# pattern_game.net
KiCad netlist of a schematic drawn in EAGLE
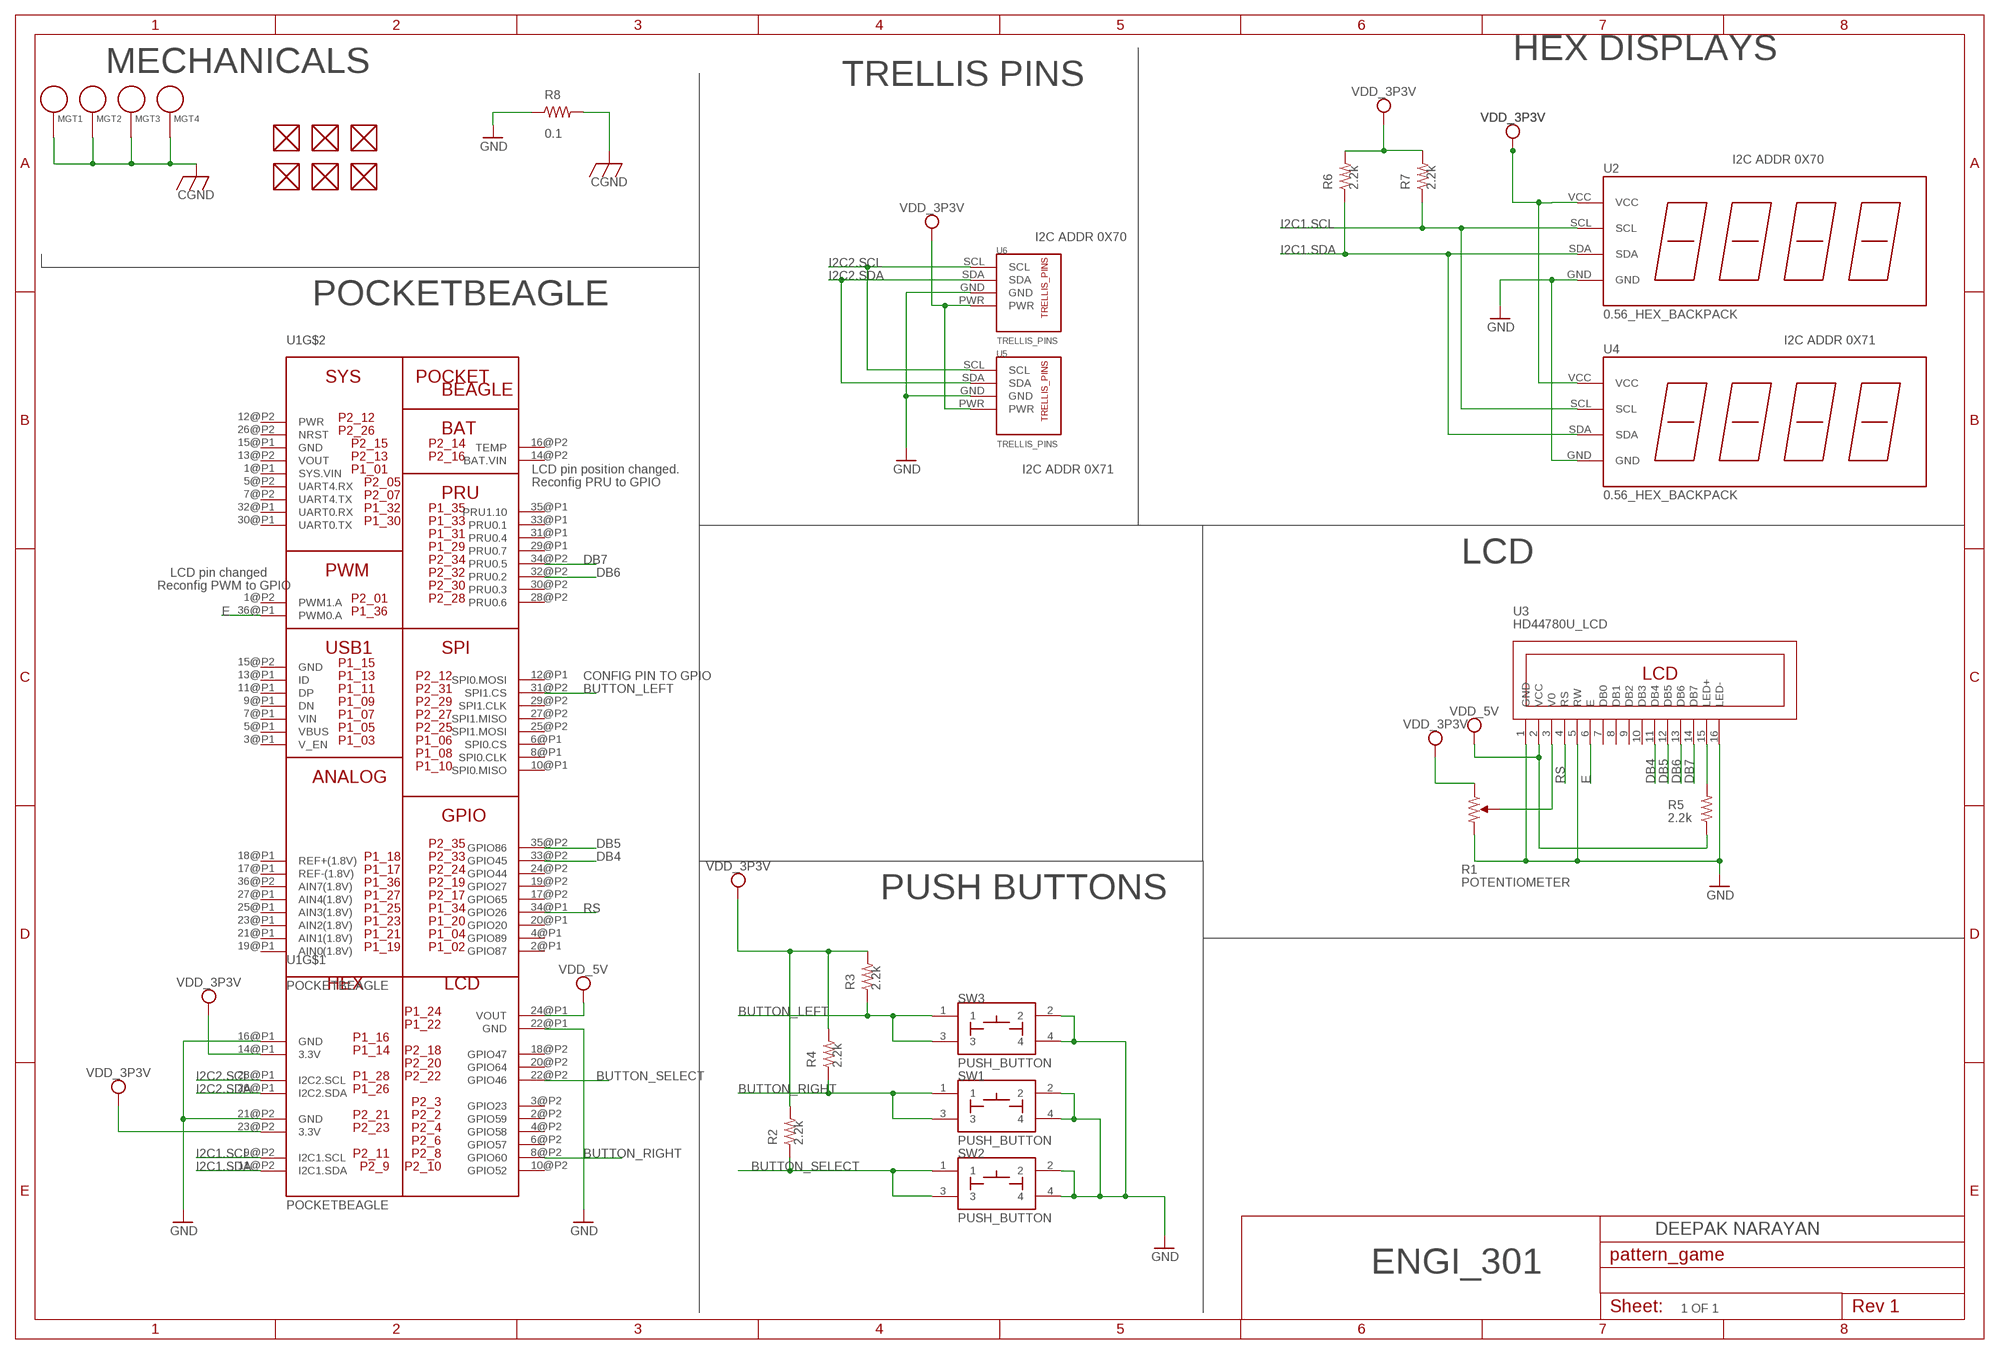
[diagram p0: schematic, sheet 1]

(export (version "E")
  (design (tool "Eeschema 10.0.6"))
  (components
    (comp (ref "FUD1")
      (value "FIDUCIAL")
      (footprint "eagle-import:FIDUCIAL_40MIL")
      (libsource (lib "eagle-import") (part "FIDUCIAL"))
    )
    (comp (ref "FUD2")
      (value "FIDUCIAL")
      (footprint "eagle-import:FIDUCIAL_40MIL")
      (libsource (lib "eagle-import") (part "FIDUCIAL"))
    )
    (comp (ref "FUD3")
      (value "FIDUCIAL")
      (footprint "eagle-import:FIDUCIAL_40MIL")
      (libsource (lib "eagle-import") (part "FIDUCIAL"))
    )
    (comp (ref "FUD4")
      (value "FIDUCIAL")
      (footprint "eagle-import:FIDUCIAL_40MIL")
      (libsource (lib "eagle-import") (part "FIDUCIAL"))
    )
    (comp (ref "FUD5")
      (value "FIDUCIAL")
      (footprint "eagle-import:FIDUCIAL_40MIL")
      (libsource (lib "eagle-import") (part "FIDUCIAL"))
    )
    (comp (ref "FUD6")
      (value "FIDUCIAL")
      (footprint "eagle-import:FIDUCIAL_40MIL")
      (libsource (lib "eagle-import") (part "FIDUCIAL"))
    )
    (comp (ref "MGT1")
      (value "MOUNTING_HOLE")
      (footprint "eagle-import:MOUNTING_HOLE")
      (libsource (lib "eagle-import") (part "MOUNTING_HOLE"))
    )
    (comp (ref "MGT2")
      (value "MOUNTING_HOLE")
      (footprint "eagle-import:MOUNTING_HOLE")
      (libsource (lib "eagle-import") (part "MOUNTING_HOLE"))
    )
    (comp (ref "MGT3")
      (value "MOUNTING_HOLE")
      (footprint "eagle-import:MOUNTING_HOLE")
      (libsource (lib "eagle-import") (part "MOUNTING_HOLE"))
    )
    (comp (ref "MGT4")
      (value "MOUNTING_HOLE")
      (footprint "eagle-import:MOUNTING_HOLE")
      (libsource (lib "eagle-import") (part "MOUNTING_HOLE"))
    )
    (comp (ref "R1")
      (value "POTENTIOMETER")
      (footprint "eagle-import:POT-PO90S")
      (libsource (lib "eagle-import") (part "POTENTIOMETER"))
    )
    (comp (ref "R2")
      (value "2.2k")
      (footprint "eagle-import:R0603")
      (libsource (lib "eagle-import") (part "R_R0603"))
    )
    (comp (ref "R3")
      (value "2.2k")
      (footprint "eagle-import:R0603")
      (libsource (lib "eagle-import") (part "R_R0603"))
    )
    (comp (ref "R4")
      (value "2.2k")
      (footprint "eagle-import:R0603")
      (libsource (lib "eagle-import") (part "R_R0603"))
    )
    (comp (ref "R5")
      (value "2.2k")
      (footprint "eagle-import:R0603")
      (libsource (lib "eagle-import") (part "R_R0603"))
    )
    (comp (ref "R6")
      (value "2.2k")
      (footprint "eagle-import:R0603")
      (libsource (lib "eagle-import") (part "R_R0603"))
    )
    (comp (ref "R7")
      (value "2.2k")
      (footprint "eagle-import:R0603")
      (libsource (lib "eagle-import") (part "R_R0603"))
    )
    (comp (ref "R8")
      (value "0.1")
      (footprint "eagle-import:R0603")
      (libsource (lib "eagle-import") (part "combo_lock_R_R0603"))
    )
    (comp (ref "SW1")
      (value "PUSH_BUTTON")
      (footprint "eagle-import:BUTTON_12.5MM")
      (libsource (lib "eagle-import") (part "PUSH_BUTTON"))
    )
    (comp (ref "SW2")
      (value "PUSH_BUTTON")
      (footprint "eagle-import:BUTTON_12.5MM")
      (libsource (lib "eagle-import") (part "PUSH_BUTTON"))
    )
    (comp (ref "SW3")
      (value "PUSH_BUTTON")
      (footprint "eagle-import:BUTTON_12.5MM")
      (libsource (lib "eagle-import") (part "PUSH_BUTTON"))
    )
    (comp (ref "U1")
      (value "POCKETBEAGLE")
      (footprint "eagle-import:POCKETBEAGLE")
      (libsource (lib "eagle-import") (part "POCKETBEAGLE"))
    )
    (comp (ref "U2")
      (value "0.56_HEX_BACKPACK")
      (footprint "eagle-import:0.56_HEX_BACKPACK")
      (libsource (lib "eagle-import") (part "0.56_HEX_BACKPACK"))
    )
    (comp (ref "U3")
      (value "HD44780U_LCD")
      (footprint "eagle-import:HD44780U_LCD")
      (libsource (lib "eagle-import") (part "HD44780U_LCD"))
    )
    (comp (ref "U4")
      (value "0.56_HEX_BACKPACK")
      (footprint "eagle-import:0.56_HEX_BACKPACK")
      (libsource (lib "eagle-import") (part "0.56_HEX_BACKPACK"))
    )
    (comp (ref "U5")
      (value "TRELLIS_PINS")
      (footprint "eagle-import:TRELLIS_PINS")
      (libsource (lib "eagle-import") (part "TRELLIS_PINS"))
    )
    (comp (ref "U6")
      (value "TRELLIS_PINS")
      (footprint "eagle-import:TRELLIS_PINS")
      (libsource (lib "eagle-import") (part "TRELLIS_PINS"))
    )
  )
  (nets
    (net (code "1") (name "/BUTTON_LEFT") (class "Default")
      (node (ref "R3") (pin "1") (pinfunction "1_1") (pintype "passive"))
      (node (ref "SW3") (pin "1") (pinfunction "1_1") (pintype "bidirectional"))
      (node (ref "SW3") (pin "3") (pinfunction "3_3") (pintype "bidirectional"))
      (node (ref "U1") (pin "31@P2") (pinfunction "SPI1.CS_31@P2") (pintype "bidirectional"))
    )
    (net (code "2") (name "/BUTTON_RIGHT") (class "Default")
      (node (ref "R4") (pin "1") (pinfunction "1_1") (pintype "passive"))
      (node (ref "SW1") (pin "1") (pinfunction "1_1") (pintype "bidirectional"))
      (node (ref "SW1") (pin "3") (pinfunction "3_3") (pintype "bidirectional"))
      (node (ref "U1") (pin "8@P2") (pinfunction "GPIO60_8@P2") (pintype "bidirectional"))
    )
    (net (code "3") (name "/BUTTON_SELECT") (class "Default")
      (node (ref "R2") (pin "1") (pinfunction "1_1") (pintype "passive"))
      (node (ref "SW2") (pin "1") (pinfunction "1_1") (pintype "bidirectional"))
      (node (ref "SW2") (pin "3") (pinfunction "3_3") (pintype "bidirectional"))
      (node (ref "U1") (pin "22@P2") (pinfunction "GPIO46_22@P2") (pintype "bidirectional"))
    )
    (net (code "4") (name "/DB4") (class "Default")
      (node (ref "U1") (pin "33@P2") (pinfunction "GPIO45_33@P2") (pintype "bidirectional"))
      (node (ref "U3") (pin "11") (pinfunction "DB4_11") (pintype "bidirectional"))
    )
    (net (code "5") (name "/DB5") (class "Default")
      (node (ref "U1") (pin "35@P2") (pinfunction "GPIO86_35@P2") (pintype "bidirectional"))
      (node (ref "U3") (pin "12") (pinfunction "DB5_12") (pintype "bidirectional"))
    )
    (net (code "6") (name "/DB6") (class "Default")
      (node (ref "U1") (pin "32@P2") (pinfunction "PRU0.2_32@P2") (pintype "bidirectional"))
      (node (ref "U3") (pin "13") (pinfunction "DB6_13") (pintype "bidirectional"))
    )
    (net (code "7") (name "/DB7") (class "Default")
      (node (ref "U1") (pin "34@P2") (pinfunction "PRU0.5_34@P2") (pintype "bidirectional"))
      (node (ref "U3") (pin "14") (pinfunction "DB7_14") (pintype "bidirectional"))
    )
    (net (code "8") (name "/E") (class "Default")
      (node (ref "U1") (pin "36@P1") (pinfunction "PWM0.A_36@P1") (pintype "bidirectional"))
      (node (ref "U3") (pin "6") (pinfunction "E_6") (pintype "bidirectional"))
    )
    (net (code "9") (name "/I2C1.SCL") (class "Default")
      (node (ref "R7") (pin "1") (pinfunction "1_1") (pintype "passive"))
      (node (ref "U1") (pin "9@P2") (pinfunction "I2C1.SCL_9@P2") (pintype "bidirectional"))
      (node (ref "U2") (pin "SCL") (pinfunction "SCL_SCL") (pintype "bidirectional"))
      (node (ref "U4") (pin "SCL") (pinfunction "SCL_SCL") (pintype "bidirectional"))
    )
    (net (code "10") (name "/I2C1.SDA") (class "Default")
      (node (ref "R6") (pin "1") (pinfunction "1_1") (pintype "passive"))
      (node (ref "U1") (pin "11@P2") (pinfunction "I2C1.SDA_11@P2") (pintype "bidirectional"))
      (node (ref "U2") (pin "SDA") (pinfunction "SDA_SDA") (pintype "bidirectional"))
      (node (ref "U4") (pin "SDA") (pinfunction "SDA_SDA") (pintype "bidirectional"))
    )
    (net (code "11") (name "/I2C2.SCL") (class "Default")
      (node (ref "U1") (pin "28@P1") (pinfunction "I2C2.SCL_28@P1") (pintype "bidirectional"))
      (node (ref "U5") (pin "SCL") (pinfunction "SCL_SCL") (pintype "bidirectional"))
      (node (ref "U6") (pin "SCL") (pinfunction "SCL_SCL") (pintype "bidirectional"))
    )
    (net (code "12") (name "/I2C2.SDA") (class "Default")
      (node (ref "U1") (pin "26@P1") (pinfunction "I2C2.SDA_26@P1") (pintype "bidirectional"))
      (node (ref "U5") (pin "SDA") (pinfunction "SDA_SDA") (pintype "bidirectional"))
      (node (ref "U6") (pin "SDA") (pinfunction "SDA_SDA") (pintype "bidirectional"))
    )
    (net (code "13") (name "/RS") (class "Default")
      (node (ref "U1") (pin "34@P1") (pinfunction "GPIO26_34@P1") (pintype "bidirectional"))
      (node (ref "U3") (pin "4") (pinfunction "RS_4") (pintype "bidirectional"))
    )
    (net (code "14") (name "CGND") (class "Default")
      (node (ref "MGT1") (pin "P$1") (pinfunction "P$1_P$1") (pintype "bidirectional"))
      (node (ref "MGT2") (pin "P$1") (pinfunction "P$1_P$1") (pintype "bidirectional"))
      (node (ref "MGT3") (pin "P$1") (pinfunction "P$1_P$1") (pintype "bidirectional"))
      (node (ref "MGT4") (pin "P$1") (pinfunction "P$1_P$1") (pintype "bidirectional"))
      (node (ref "R8") (pin "2") (pinfunction "2_2") (pintype "passive"))
    )
    (net (code "15") (name "GND") (class "Default")
      (node (ref "R1") (pin "CW") (pinfunction "CW_CW") (pintype "passive"))
      (node (ref "R8") (pin "1") (pinfunction "1_1") (pintype "passive"))
      (node (ref "SW1") (pin "2") (pinfunction "2_2") (pintype "bidirectional"))
      (node (ref "SW1") (pin "4") (pinfunction "4_4") (pintype "bidirectional"))
      (node (ref "SW2") (pin "2") (pinfunction "2_2") (pintype "bidirectional"))
      (node (ref "SW2") (pin "4") (pinfunction "4_4") (pintype "bidirectional"))
      (node (ref "SW3") (pin "2") (pinfunction "2_2") (pintype "bidirectional"))
      (node (ref "SW3") (pin "4") (pinfunction "4_4") (pintype "bidirectional"))
      (node (ref "U1") (pin "16@P1") (pinfunction "GND_16@P1") (pintype "power_in"))
      (node (ref "U1") (pin "21@P2") (pinfunction "GND_21@P2") (pintype "power_in"))
      (node (ref "U1") (pin "22@P1") (pinfunction "GND_22@P1") (pintype "power_in"))
      (node (ref "U2") (pin "GND") (pinfunction "GND_GND") (pintype "bidirectional"))
      (node (ref "U3") (pin "1") (pinfunction "GND_1") (pintype "power_in"))
      (node (ref "U3") (pin "16") (pinfunction "LED-_16") (pintype "power_in"))
      (node (ref "U3") (pin "5") (pinfunction "RW_5") (pintype "bidirectional"))
      (node (ref "U4") (pin "GND") (pinfunction "GND_GND") (pintype "bidirectional"))
      (node (ref "U5") (pin "GND") (pinfunction "GND_GND") (pintype "bidirectional"))
      (node (ref "U6") (pin "GND") (pinfunction "GND_GND") (pintype "bidirectional"))
    )
    (net (code "16") (name "Net-(U3-LED+)") (class "Default")
      (node (ref "R5") (pin "2") (pinfunction "2_2") (pintype "passive"))
      (node (ref "U3") (pin "15") (pinfunction "LED+_15") (pintype "power_in"))
    )
    (net (code "17") (name "Net-(U3-V0)") (class "Default")
      (node (ref "R1") (pin "S") (pinfunction "S_S") (pintype "bidirectional"))
      (node (ref "U3") (pin "3") (pinfunction "V0_3") (pintype "bidirectional"))
    )
    (net (code "18") (name "VDD_3P3V") (class "Default")
      (node (ref "R1") (pin "CCW") (pinfunction "CCW_CCW") (pintype "passive"))
      (node (ref "R2") (pin "2") (pinfunction "2_2") (pintype "passive"))
      (node (ref "R3") (pin "2") (pinfunction "2_2") (pintype "passive"))
      (node (ref "R4") (pin "2") (pinfunction "2_2") (pintype "passive"))
      (node (ref "R6") (pin "2") (pinfunction "2_2") (pintype "passive"))
      (node (ref "R7") (pin "2") (pinfunction "2_2") (pintype "passive"))
      (node (ref "U1") (pin "14@P1") (pinfunction "3.3V_14@P1") (pintype "power_in"))
      (node (ref "U1") (pin "23@P2") (pinfunction "3.3V_23@P2") (pintype "power_in"))
      (node (ref "U2") (pin "VCC") (pinfunction "VCC_VCC") (pintype "power_in"))
      (node (ref "U4") (pin "VCC") (pinfunction "VCC_VCC") (pintype "power_in"))
      (node (ref "U5") (pin "PWR") (pinfunction "PWR_PWR") (pintype "bidirectional"))
      (node (ref "U6") (pin "PWR") (pinfunction "PWR_PWR") (pintype "bidirectional"))
    )
    (net (code "19") (name "VDD_5V") (class "Default")
      (node (ref "R5") (pin "1") (pinfunction "1_1") (pintype "passive"))
      (node (ref "U1") (pin "24@P1") (pinfunction "VOUT_24@P1") (pintype "power_in"))
      (node (ref "U3") (pin "2") (pinfunction "VCC_2") (pintype "power_in"))
    )
    (net (code "20") (name "unconnected-(FUD1-PadP$1)") (class "Default")
      (node (ref "FUD1") (pin "P$1") (pinfunction "P$1_P$1") (pintype "no_connect"))
    )
    (net (code "21") (name "unconnected-(FUD2-PadP$1)") (class "Default")
      (node (ref "FUD2") (pin "P$1") (pinfunction "P$1_P$1") (pintype "no_connect"))
    )
    (net (code "22") (name "unconnected-(FUD3-PadP$1)") (class "Default")
      (node (ref "FUD3") (pin "P$1") (pinfunction "P$1_P$1") (pintype "no_connect"))
    )
    (net (code "23") (name "unconnected-(FUD4-PadP$1)") (class "Default")
      (node (ref "FUD4") (pin "P$1") (pinfunction "P$1_P$1") (pintype "no_connect"))
    )
    (net (code "24") (name "unconnected-(FUD5-PadP$1)") (class "Default")
      (node (ref "FUD5") (pin "P$1") (pinfunction "P$1_P$1") (pintype "no_connect"))
    )
    (net (code "25") (name "unconnected-(FUD6-PadP$1)") (class "Default")
      (node (ref "FUD6") (pin "P$1") (pinfunction "P$1_P$1") (pintype "no_connect"))
    )
    (net (code "26") (name "unconnected-(U1A-GPIO23-Pad3@P2)") (class "Default")
      (node (ref "U1") (pin "3@P2") (pinfunction "GPIO23_3@P2") (pintype "bidirectional"))
    )
    (net (code "27") (name "unconnected-(U1A-GPIO47-Pad18@P2)") (class "Default")
      (node (ref "U1") (pin "18@P2") (pinfunction "GPIO47_18@P2") (pintype "bidirectional"))
    )
    (net (code "28") (name "unconnected-(U1A-GPIO52-Pad10@P2)") (class "Default")
      (node (ref "U1") (pin "10@P2") (pinfunction "GPIO52_10@P2") (pintype "bidirectional"))
    )
    (net (code "29") (name "unconnected-(U1A-GPIO57-Pad6@P2)") (class "Default")
      (node (ref "U1") (pin "6@P2") (pinfunction "GPIO57_6@P2") (pintype "bidirectional"))
    )
    (net (code "30") (name "unconnected-(U1A-GPIO58-Pad4@P2)") (class "Default")
      (node (ref "U1") (pin "4@P2") (pinfunction "GPIO58_4@P2") (pintype "bidirectional"))
    )
    (net (code "31") (name "unconnected-(U1A-GPIO59-Pad2@P2)") (class "Default")
      (node (ref "U1") (pin "2@P2") (pinfunction "GPIO59_2@P2") (pintype "bidirectional"))
    )
    (net (code "32") (name "unconnected-(U1A-GPIO64-Pad20@P2)") (class "Default")
      (node (ref "U1") (pin "20@P2") (pinfunction "GPIO64_20@P2") (pintype "bidirectional"))
    )
    (net (code "33") (name "unconnected-(U1B-AIN0(1.8V)-Pad19@P1)") (class "Default")
      (node (ref "U1") (pin "19@P1") (pinfunction "AIN0(1.8V)_19@P1") (pintype "bidirectional"))
    )
    (net (code "34") (name "unconnected-(U1B-AIN1(1.8V)-Pad21@P1)") (class "Default")
      (node (ref "U1") (pin "21@P1") (pinfunction "AIN1(1.8V)_21@P1") (pintype "bidirectional"))
    )
    (net (code "35") (name "unconnected-(U1B-AIN2(1.8V)-Pad23@P1)") (class "Default")
      (node (ref "U1") (pin "23@P1") (pinfunction "AIN2(1.8V)_23@P1") (pintype "bidirectional"))
    )
    (net (code "36") (name "unconnected-(U1B-AIN3(1.8V)-Pad25@P1)") (class "Default")
      (node (ref "U1") (pin "25@P1") (pinfunction "AIN3(1.8V)_25@P1") (pintype "bidirectional"))
    )
    (net (code "37") (name "unconnected-(U1B-AIN4(1.8V)-Pad27@P1)") (class "Default")
      (node (ref "U1") (pin "27@P1") (pinfunction "AIN4(1.8V)_27@P1") (pintype "bidirectional"))
    )
    (net (code "38") (name "unconnected-(U1B-AIN7(1.8V)-Pad36@P2)") (class "Default")
      (node (ref "U1") (pin "36@P2") (pinfunction "AIN7(1.8V)_36@P2") (pintype "bidirectional"))
    )
    (net (code "39") (name "unconnected-(U1B-BAT.VIN-Pad14@P2)") (class "Default")
      (node (ref "U1") (pin "14@P2") (pinfunction "BAT.VIN_14@P2") (pintype "bidirectional"))
    )
    (net (code "40") (name "unconnected-(U1B-DN-Pad9@P1)") (class "Default")
      (node (ref "U1") (pin "9@P1") (pinfunction "DN_9@P1") (pintype "bidirectional"))
    )
    (net (code "41") (name "unconnected-(U1B-DP-Pad11@P1)") (class "Default")
      (node (ref "U1") (pin "11@P1") (pinfunction "DP_11@P1") (pintype "bidirectional"))
    )
    (net (code "42") (name "unconnected-(U1B-GND-Pad15@P1)") (class "Default")
      (node (ref "U1") (pin "15@P1") (pinfunction "GND_15@P1") (pintype "bidirectional"))
    )
    (net (code "43") (name "unconnected-(U1B-GND-Pad15@P2)") (class "Default")
      (node (ref "U1") (pin "15@P2") (pinfunction "GND_15@P2") (pintype "bidirectional"))
    )
    (net (code "44") (name "unconnected-(U1B-GPIO20-Pad20@P1)") (class "Default")
      (node (ref "U1") (pin "20@P1") (pinfunction "GPIO20_20@P1") (pintype "bidirectional"))
    )
    (net (code "45") (name "unconnected-(U1B-GPIO27-Pad19@P2)") (class "Default")
      (node (ref "U1") (pin "19@P2") (pinfunction "GPIO27_19@P2") (pintype "bidirectional"))
    )
    (net (code "46") (name "unconnected-(U1B-GPIO44-Pad24@P2)") (class "Default")
      (node (ref "U1") (pin "24@P2") (pinfunction "GPIO44_24@P2") (pintype "bidirectional"))
    )
    (net (code "47") (name "unconnected-(U1B-GPIO65-Pad17@P2)") (class "Default")
      (node (ref "U1") (pin "17@P2") (pinfunction "GPIO65_17@P2") (pintype "bidirectional"))
    )
    (net (code "48") (name "unconnected-(U1B-GPIO87-Pad2@P1)") (class "Default")
      (node (ref "U1") (pin "2@P1") (pinfunction "GPIO87_2@P1") (pintype "bidirectional"))
    )
    (net (code "49") (name "unconnected-(U1B-GPIO89-Pad4@P1)") (class "Default")
      (node (ref "U1") (pin "4@P1") (pinfunction "GPIO89_4@P1") (pintype "bidirectional"))
    )
    (net (code "50") (name "unconnected-(U1B-ID-Pad13@P1)") (class "Default")
      (node (ref "U1") (pin "13@P1") (pinfunction "ID_13@P1") (pintype "bidirectional"))
    )
    (net (code "51") (name "unconnected-(U1B-NRST-Pad26@P2)") (class "Default")
      (node (ref "U1") (pin "26@P2") (pinfunction "NRST_26@P2") (pintype "bidirectional"))
    )
    (net (code "52") (name "unconnected-(U1B-PRU0.1-Pad33@P1)") (class "Default")
      (node (ref "U1") (pin "33@P1") (pinfunction "PRU0.1_33@P1") (pintype "bidirectional"))
    )
    (net (code "53") (name "unconnected-(U1B-PRU0.3-Pad30@P2)") (class "Default")
      (node (ref "U1") (pin "30@P2") (pinfunction "PRU0.3_30@P2") (pintype "bidirectional"))
    )
    (net (code "54") (name "unconnected-(U1B-PRU0.4-Pad31@P1)") (class "Default")
      (node (ref "U1") (pin "31@P1") (pinfunction "PRU0.4_31@P1") (pintype "bidirectional"))
    )
    (net (code "55") (name "unconnected-(U1B-PRU0.6-Pad28@P2)") (class "Default")
      (node (ref "U1") (pin "28@P2") (pinfunction "PRU0.6_28@P2") (pintype "bidirectional"))
    )
    (net (code "56") (name "unconnected-(U1B-PRU0.7-Pad29@P1)") (class "Default")
      (node (ref "U1") (pin "29@P1") (pinfunction "PRU0.7_29@P1") (pintype "bidirectional"))
    )
    (net (code "57") (name "unconnected-(U1B-PRU1.10-Pad35@P1)") (class "Default")
      (node (ref "U1") (pin "35@P1") (pinfunction "PRU1.10_35@P1") (pintype "bidirectional"))
    )
    (net (code "58") (name "unconnected-(U1B-PWM1.A-Pad1@P2)") (class "Default")
      (node (ref "U1") (pin "1@P2") (pinfunction "PWM1.A_1@P2") (pintype "bidirectional"))
    )
    (net (code "59") (name "unconnected-(U1B-PWR-Pad12@P2)") (class "Default")
      (node (ref "U1") (pin "12@P2") (pinfunction "PWR_12@P2") (pintype "bidirectional"))
    )
    (net (code "60") (name "unconnected-(U1B-REF+(1.8V)-Pad18@P1)") (class "Default")
      (node (ref "U1") (pin "18@P1") (pinfunction "REF+(1.8V)_18@P1") (pintype "bidirectional"))
    )
    (net (code "61") (name "unconnected-(U1B-REF-(1.8V)-Pad17@P1)") (class "Default")
      (node (ref "U1") (pin "17@P1") (pinfunction "REF-(1.8V)_17@P1") (pintype "bidirectional"))
    )
    (net (code "62") (name "unconnected-(U1B-SPI0.CLK-Pad8@P1)") (class "Default")
      (node (ref "U1") (pin "8@P1") (pinfunction "SPI0.CLK_8@P1") (pintype "bidirectional"))
    )
    (net (code "63") (name "unconnected-(U1B-SPI0.CS-Pad6@P1)") (class "Default")
      (node (ref "U1") (pin "6@P1") (pinfunction "SPI0.CS_6@P1") (pintype "bidirectional"))
    )
    (net (code "64") (name "unconnected-(U1B-SPI0.MISO-Pad10@P1)") (class "Default")
      (node (ref "U1") (pin "10@P1") (pinfunction "SPI0.MISO_10@P1") (pintype "bidirectional"))
    )
    (net (code "65") (name "unconnected-(U1B-SPI0.MOSI-Pad12@P1)") (class "Default")
      (node (ref "U1") (pin "12@P1") (pinfunction "SPI0.MOSI_12@P1") (pintype "bidirectional"))
    )
    (net (code "66") (name "unconnected-(U1B-SPI1.CLK-Pad29@P2)") (class "Default")
      (node (ref "U1") (pin "29@P2") (pinfunction "SPI1.CLK_29@P2") (pintype "bidirectional"))
    )
    (net (code "67") (name "unconnected-(U1B-SPI1.MISO-Pad27@P2)") (class "Default")
      (node (ref "U1") (pin "27@P2") (pinfunction "SPI1.MISO_27@P2") (pintype "bidirectional"))
    )
    (net (code "68") (name "unconnected-(U1B-SPI1.MOSI-Pad25@P2)") (class "Default")
      (node (ref "U1") (pin "25@P2") (pinfunction "SPI1.MOSI_25@P2") (pintype "bidirectional"))
    )
    (net (code "69") (name "unconnected-(U1B-SYS.VIN-Pad1@P1)") (class "Default")
      (node (ref "U1") (pin "1@P1") (pinfunction "SYS.VIN_1@P1") (pintype "bidirectional"))
    )
    (net (code "70") (name "unconnected-(U1B-TEMP-Pad16@P2)") (class "Default")
      (node (ref "U1") (pin "16@P2") (pinfunction "TEMP_16@P2") (pintype "bidirectional"))
    )
    (net (code "71") (name "unconnected-(U1B-UART0.RX-Pad32@P1)") (class "Default")
      (node (ref "U1") (pin "32@P1") (pinfunction "UART0.RX_32@P1") (pintype "bidirectional"))
    )
    (net (code "72") (name "unconnected-(U1B-UART0.TX-Pad30@P1)") (class "Default")
      (node (ref "U1") (pin "30@P1") (pinfunction "UART0.TX_30@P1") (pintype "bidirectional"))
    )
    (net (code "73") (name "unconnected-(U1B-UART4.RX-Pad5@P2)") (class "Default")
      (node (ref "U1") (pin "5@P2") (pinfunction "UART4.RX_5@P2") (pintype "bidirectional"))
    )
    (net (code "74") (name "unconnected-(U1B-UART4.TX-Pad7@P2)") (class "Default")
      (node (ref "U1") (pin "7@P2") (pinfunction "UART4.TX_7@P2") (pintype "bidirectional"))
    )
    (net (code "75") (name "unconnected-(U1B-VBUS-Pad5@P1)") (class "Default")
      (node (ref "U1") (pin "5@P1") (pinfunction "VBUS_5@P1") (pintype "bidirectional"))
    )
    (net (code "76") (name "unconnected-(U1B-VIN-Pad7@P1)") (class "Default")
      (node (ref "U1") (pin "7@P1") (pinfunction "VIN_7@P1") (pintype "bidirectional"))
    )
    (net (code "77") (name "unconnected-(U1B-VOUT-Pad13@P2)") (class "Default")
      (node (ref "U1") (pin "13@P2") (pinfunction "VOUT_13@P2") (pintype "bidirectional"))
    )
    (net (code "78") (name "unconnected-(U1B-V_EN-Pad3@P1)") (class "Default")
      (node (ref "U1") (pin "3@P1") (pinfunction "V_EN_3@P1") (pintype "bidirectional"))
    )
    (net (code "79") (name "unconnected-(U3-DB0-Pad7)") (class "Default")
      (node (ref "U3") (pin "7") (pinfunction "DB0_7") (pintype "bidirectional"))
    )
    (net (code "80") (name "unconnected-(U3-DB1-Pad8)") (class "Default")
      (node (ref "U3") (pin "8") (pinfunction "DB1_8") (pintype "bidirectional"))
    )
    (net (code "81") (name "unconnected-(U3-DB2-Pad9)") (class "Default")
      (node (ref "U3") (pin "9") (pinfunction "DB2_9") (pintype "bidirectional"))
    )
    (net (code "82") (name "unconnected-(U3-DB3-Pad10)") (class "Default")
      (node (ref "U3") (pin "10") (pinfunction "DB3_10") (pintype "bidirectional"))
    )
  )
)
